# Charging_Controller_STM32_Base.net
KiCad netlist of a schematic drawn in EAGLE
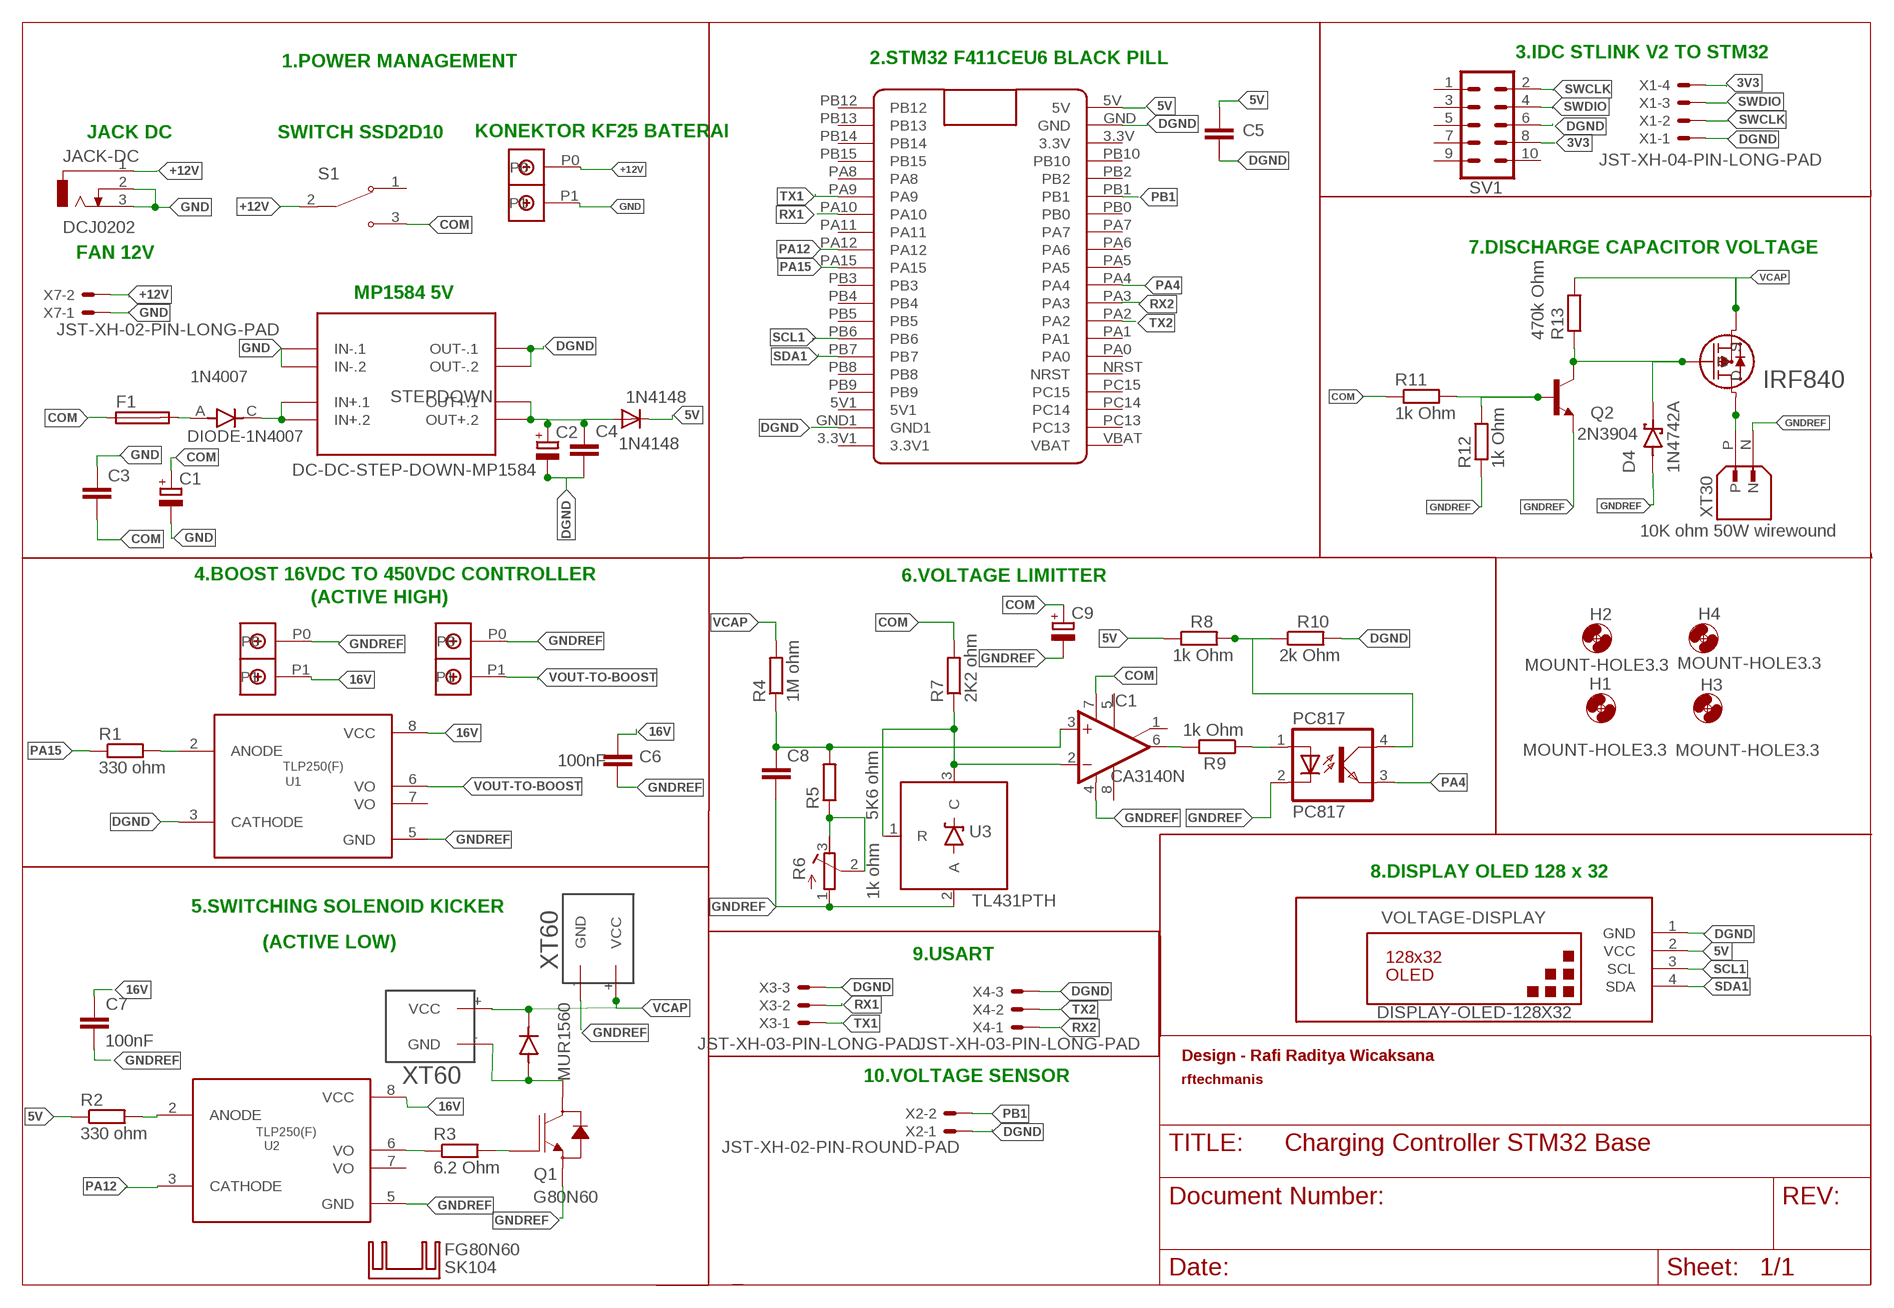
[diagram p0: schematic, sheet 1, part 1 of 2]
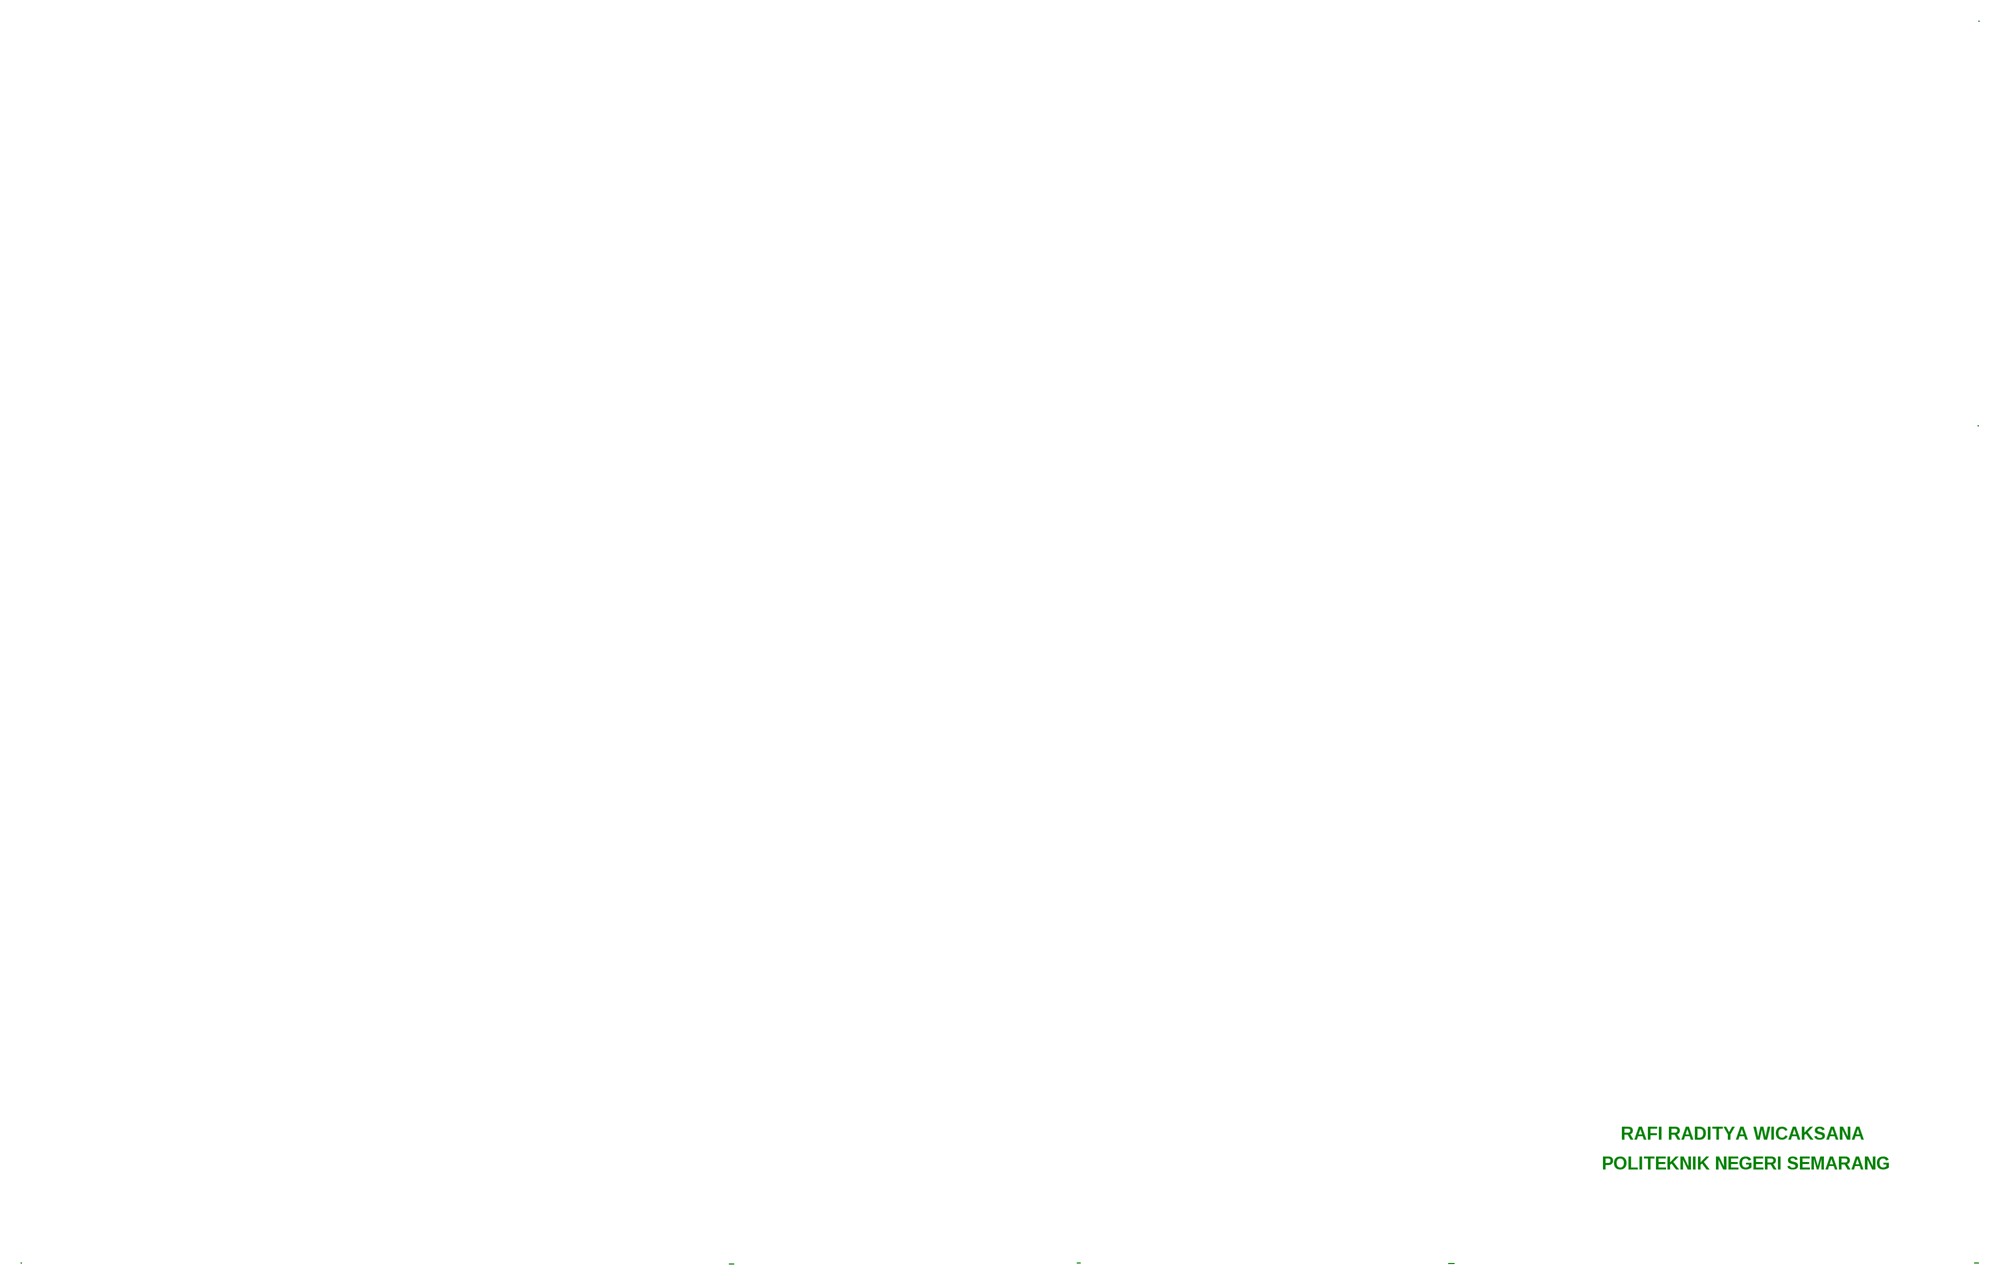
[diagram p1: schematic, sheet 1, part 2 of 2]

(export (version "E")
  (design (tool "Eeschema 10.0.6"))
  (components
    (comp (ref "1N4007")
      (value "DIODE-1N4007")
      (footprint "eagle-import:DIOAD1060W80L520D270")
      (fields (field (name "MF") "Diotec Semiconductor") (field (name "MP") "1N4007"))
      (libsource (lib "eagle-import") (part "DIODE-1N4007"))
    )
    (comp (ref "1N4148")
      (value "1N4148")
      (footprint "eagle-import:DO35-10")
      (libsource (lib "eagle-import") (part "1N4148"))
    )
    (comp (ref "C1")
      (value "CPOL-EUE3.5-8")
      (footprint "eagle-import:E3,5-8")
      (libsource (lib "eagle-import") (part "CPOL-EUE3.5-8"))
    )
    (comp (ref "C2")
      (value "CPOL-EUE3.5-8")
      (footprint "eagle-import:E3,5-8")
      (libsource (lib "eagle-import") (part "CPOL-EUE3.5-8"))
    )
    (comp (ref "C3")
      (value "C-EU050-030X075")
      (footprint "eagle-import:C050-030X075")
      (libsource (lib "eagle-import") (part "C-EU050-030X075"))
    )
    (comp (ref "C4")
      (value "C-EU050-030X075")
      (footprint "eagle-import:C050-030X075")
      (libsource (lib "eagle-import") (part "C-EU050-030X075"))
    )
    (comp (ref "C5")
      (value "C-EU050-030X075")
      (footprint "eagle-import:C050-030X075")
      (libsource (lib "eagle-import") (part "C-EU050-030X075"))
    )
    (comp (ref "C6")
      (value "100nF")
      (footprint "eagle-import:C050-030X075")
      (libsource (lib "eagle-import") (part "C-EU050-030X075"))
    )
    (comp (ref "C7")
      (value "100nF")
      (footprint "eagle-import:C050-030X075")
      (libsource (lib "eagle-import") (part "C-EU050-030X075"))
    )
    (comp (ref "C8")
      (value "C-EU050-035X075")
      (footprint "eagle-import:C050-035X075")
      (libsource (lib "eagle-import") (part "C-EU050-035X075"))
    )
    (comp (ref "C9")
      (value "CPOL-EUE2-5")
      (footprint "eagle-import:E2-5")
      (libsource (lib "eagle-import") (part "CPOL-EUE2-5"))
    )
    (comp (ref "D4")
      (value "1N4742A")
      (footprint "eagle-import:DIOAD1036W78L463D237")
      (fields (field (name "MF") "ON"))
      (libsource (lib "eagle-import") (part "1N4742A"))
    )
    (comp (ref "F1")
      (value "SH25")
      (footprint "eagle-import:SH25")
      (fields (field (name "MF") "SCHURTER") (field (name "MPN") "0031.8211"))
      (libsource (lib "eagle-import") (part "SH25"))
    )
    (comp (ref "FG80N60")
      (value "SK104")
      (footprint "eagle-import:SK104")
      (libsource (lib "eagle-import") (part "SK104"))
    )
    (comp (ref "H1")
      (value "MOUNT-HOLE3.3")
      (footprint "eagle-import:3,3")
      (libsource (lib "eagle-import") (part "MOUNT-HOLE3.3"))
    )
    (comp (ref "H2")
      (value "MOUNT-HOLE3.3")
      (footprint "eagle-import:3,3")
      (libsource (lib "eagle-import") (part "MOUNT-HOLE3.3"))
    )
    (comp (ref "H3")
      (value "MOUNT-HOLE3.3")
      (footprint "eagle-import:3,3")
      (libsource (lib "eagle-import") (part "MOUNT-HOLE3.3"))
    )
    (comp (ref "H4")
      (value "MOUNT-HOLE3.3")
      (footprint "eagle-import:3,3")
      (libsource (lib "eagle-import") (part "MOUNT-HOLE3.3"))
    )
    (comp (ref "IC1")
      (value "CA3140N")
      (footprint "eagle-import:DIL08")
      (libsource (lib "eagle-import") (part "CA3140N"))
    )
    (comp (ref "JACK-DC")
      (value "DCJ0202")
      (footprint "eagle-import:DCJ0202")
      (libsource (lib "eagle-import") (part "DCJ0202"))
    )
    (comp (ref "KF25_2PIN3")
      (value "KF25_2PIN")
      (footprint "eagle-import:KF25_2PIN")
      (libsource (lib "eagle-import") (part "KF25_2PIN"))
    )
    (comp (ref "KF25_2PIN4")
      (value "KF25_2PIN")
      (footprint "eagle-import:KF25_2PIN")
      (libsource (lib "eagle-import") (part "KF25_2PIN"))
    )
    (comp (ref "MUR1560")
      (value "MUR1560")
      (footprint "eagle-import:TO508P997X444X1905-2")
      (fields (field (name "MF") "Diotec Semiconductor"))
      (libsource (lib "eagle-import") (part "MUR1560"))
    )
    (comp (ref "PC817")
      (value "PC817")
      (footprint "eagle-import:DIL04")
      (libsource (lib "eagle-import") (part "PC817"))
    )
    (comp (ref "Q1")
      (value "G80N60")
      (footprint "eagle-import:TO544P1613X521X2557-3")
      (fields (field (name "MF") "Infineon Technologies"))
      (libsource (lib "eagle-import") (part "G80N60"))
    )
    (comp (ref "Q2")
      (value "2N3904")
      (footprint "eagle-import:TO92")
      (libsource (lib "eagle-import") (part "2N3904"))
    )
    (comp (ref "R1")
      (value "330 ohm")
      (footprint "eagle-import:0204_7")
      (libsource (lib "eagle-import") (part "R-EU_0204/7"))
    )
    (comp (ref "R2")
      (value "330 ohm")
      (footprint "eagle-import:0204_7")
      (libsource (lib "eagle-import") (part "R-EU_0204/7"))
    )
    (comp (ref "R3")
      (value "6.2 Ohm")
      (footprint "eagle-import:0411_12")
      (libsource (lib "eagle-import") (part "R-EU_0411/12"))
    )
    (comp (ref "R4")
      (value "1M ohm")
      (footprint "eagle-import:0411_12")
      (libsource (lib "eagle-import") (part "R-EU_0411/12"))
    )
    (comp (ref "R5")
      (value "5K6 ohm")
      (footprint "eagle-import:0411_12")
      (libsource (lib "eagle-import") (part "R-EU_0411/12"))
    )
    (comp (ref "R6")
      (value "1k ohm")
      (footprint "eagle-import:RTRIM64X")
      (libsource (lib "eagle-import") (part "R-TRIMM64X"))
    )
    (comp (ref "R7")
      (value "2K2 ohm")
      (footprint "eagle-import:0207_10")
      (libsource (lib "eagle-import") (part "R-EU_0207/10"))
    )
    (comp (ref "R8")
      (value "1k Ohm")
      (footprint "eagle-import:0207_10")
      (libsource (lib "eagle-import") (part "R-EU_0207/10"))
    )
    (comp (ref "R9")
      (value "1k Ohm")
      (footprint "eagle-import:0207_10")
      (libsource (lib "eagle-import") (part "R-EU_0207/10"))
    )
    (comp (ref "R10")
      (value "2k Ohm")
      (footprint "eagle-import:0207_10")
      (libsource (lib "eagle-import") (part "R-EU_0207/10"))
    )
    (comp (ref "R11")
      (value "1k Ohm")
      (footprint "eagle-import:0204_7")
      (libsource (lib "eagle-import") (part "R-EU_0204/7"))
    )
    (comp (ref "R12")
      (value "1k Ohm")
      (footprint "eagle-import:0204_7")
      (libsource (lib "eagle-import") (part "R-EU_0204/7"))
    )
    (comp (ref "R13")
      (value "470k Ohm")
      (footprint "eagle-import:0204_7")
      (libsource (lib "eagle-import") (part "R-EU_0204/7"))
    )
    (comp (ref "S1")
      (value "1103M2S3CQE2")
      (footprint "eagle-import:SW_1103M2S3CQE2")
      (fields (field (name "MF") "C&K"))
      (libsource (lib "eagle-import") (part "1103M2S3CQE2"))
    )
    (comp (ref "STEPDOWN")
      (value "DC-DC-STEP-DOWN-MP1584")
      (footprint "eagle-import:DC-DC-STEP-DOWN-MP1584")
      (libsource (lib "eagle-import") (part "DC-DC-STEP-DOWN-MP1584"))
    )
    (comp (ref "SV1")
      (value "ML10")
      (footprint "eagle-import:ML10")
      (libsource (lib "eagle-import") (part "ML10"))
    )
    (comp (ref "U$2")
      (value "KF25_2PIN")
      (footprint "eagle-import:KF25_2PIN")
      (libsource (lib "eagle-import") (part "KF25_2PIN"))
    )
    (comp (ref "U$3")
      (value "BLACK_PILL")
      (footprint "eagle-import:BLACK_PILL")
      (libsource (lib "eagle-import") (part "BLACK_PILL"))
    )
    (comp (ref "U$4")
      (value "XT60")
      (footprint "eagle-import:XT60")
      (libsource (lib "eagle-import") (part "XT60"))
    )
    (comp (ref "U$5")
      (value "XT60")
      (footprint "eagle-import:XT60")
      (libsource (lib "eagle-import") (part "XT60"))
    )
    (comp (ref "U1")
      (value "TLP250(F)")
      (footprint "eagle-import:DIP1016W50P254L966H380Q8P")
      (fields (field (name "MF") "Toshiba"))
      (libsource (lib "eagle-import") (part "TLP250(F)"))
    )
    (comp (ref "U2")
      (value "TLP250(F)")
      (footprint "eagle-import:DIP1016W50P254L966H380Q8P")
      (fields (field (name "MF") "Toshiba"))
      (libsource (lib "eagle-import") (part "TLP250(F)"))
    )
    (comp (ref "U3")
      (value "TL431PTH")
      (footprint "eagle-import:TO-92")
      (fields (field (name "MF") "onsemi") (field (name "MP") "TL431"))
      (libsource (lib "eagle-import") (part "TL431PTH"))
    )
    (comp (ref "U4")
      (value "IRF840")
      (footprint "eagle-import:TO220AB_VIS")
      (fields (field (name "COPYRIGHT") "Copyright (C) 2026 Ultra Librarian. All rights reserved."))
      (libsource (lib "eagle-import") (part "IRF840"))
    )
    (comp (ref "VOLTAGE-DISPLAY")
      (value "DISPLAY-OLED-128X32")
      (footprint "eagle-import:DISPLAY-OLED-128X32")
      (libsource (lib "eagle-import") (part "DISPLAY-OLED-128X32"))
    )
    (comp (ref "X1")
      (value "JST-XH-04-PIN-LONG-PAD")
      (footprint "eagle-import:JST-XH-04-PACKAGE-LONG-PAD")
      (libsource (lib "eagle-import") (part "JST-XH-04-PIN-LONG-PAD"))
    )
    (comp (ref "X2")
      (value "JST-XH-02-PIN-ROUND-PAD")
      (footprint "eagle-import:JST-XH-02-PACKAGE-ROUND-PAD")
      (libsource (lib "eagle-import") (part "JST-XH-02-PIN-ROUND-PAD"))
    )
    (comp (ref "X3")
      (value "JST-XH-03-PIN-LONG-PAD")
      (footprint "eagle-import:JST-XH-03-PACKAGE-LONG-PAD")
      (libsource (lib "eagle-import") (part "JST-XH-03-PIN-LONG-PAD"))
    )
    (comp (ref "X4")
      (value "JST-XH-03-PIN-LONG-PAD")
      (footprint "eagle-import:JST-XH-03-PACKAGE-LONG-PAD")
      (libsource (lib "eagle-import") (part "JST-XH-03-PIN-LONG-PAD"))
    )
    (comp (ref "X7")
      (value "JST-XH-02-PIN-LONG-PAD")
      (footprint "eagle-import:JST-XH-02-PACKAGE-LONG-PAD")
      (libsource (lib "eagle-import") (part "JST-XH-02-PIN-LONG-PAD"))
    )
    (comp (ref "XT30")
      (value "10K ohm 50W wirewound")
      (footprint "eagle-import:AMASS_XT30PW-M")
      (fields (field (name "MF") "AMASS") (field (name "MP") "XT30PW-M"))
      (libsource (lib "eagle-import") (part "XT30PW-M"))
    )
  )
  (nets
    (net (code "1") (name "+12V") (class "Default")
      (node (ref "JACK-DC") (pin "1") (pinfunction "1_1") (pintype "passive"))
      (node (ref "S1") (pin "2") (pinfunction "2_2") (pintype "passive"))
      (node (ref "U$2") (pin "P0") (pinfunction "P0_P0") (pintype "bidirectional"))
      (node (ref "X7") (pin "2") (pinfunction "S_2") (pintype "passive"))
    )
    (net (code "2") (name "3V3") (class "Default")
      (node (ref "SV1") (pin "8") (pinfunction "8_8") (pintype "passive"))
      (node (ref "X1") (pin "4") (pinfunction "S_4") (pintype "passive"))
    )
    (net (code "3") (name "5V") (class "Default")
      (node (ref "1N4148") (pin "C") (pinfunction "C_C") (pintype "passive"))
      (node (ref "C5") (pin "1") (pinfunction "1_1") (pintype "passive"))
      (node (ref "R2") (pin "1") (pinfunction "1_1") (pintype "passive"))
      (node (ref "R8") (pin "1") (pinfunction "1_1") (pintype "passive"))
      (node (ref "U$3") (pin "5V") (pinfunction "5V_5V") (pintype "power_in"))
      (node (ref "VOLTAGE-DISPLAY") (pin "2") (pinfunction "VCC_2") (pintype "power_in"))
    )
    (net (code "4") (name "16V") (class "Default")
      (node (ref "C6") (pin "1") (pinfunction "1_1") (pintype "passive"))
      (node (ref "C7") (pin "1") (pinfunction "1_1") (pintype "passive"))
      (node (ref "KF25_2PIN3") (pin "P1") (pinfunction "P1_P1") (pintype "bidirectional"))
      (node (ref "U1") (pin "8") (pinfunction "VCC_8") (pintype "power_in"))
      (node (ref "U2") (pin "8") (pinfunction "VCC_8") (pintype "power_in"))
    )
    (net (code "5") (name "COM") (class "Default")
      (node (ref "C1") (pin "+") (pinfunction "+_+") (pintype "passive"))
      (node (ref "C3") (pin "2") (pinfunction "2_2") (pintype "passive"))
      (node (ref "C9") (pin "+") (pinfunction "+_+") (pintype "passive"))
      (node (ref "F1") (pin "1") (pinfunction "1_1") (pintype "passive"))
      (node (ref "IC1") (pin "7") (pinfunction "V+_7") (pintype "power_in"))
      (node (ref "R11") (pin "1") (pinfunction "1_1") (pintype "passive"))
      (node (ref "R7") (pin "2") (pinfunction "2_2") (pintype "passive"))
      (node (ref "S1") (pin "3") (pinfunction "3_3") (pintype "passive"))
    )
    (net (code "6") (name "DGND") (class "Default")
      (node (ref "C2") (pin "-") (pinfunction "-_-") (pintype "passive"))
      (node (ref "C4") (pin "2") (pinfunction "2_2") (pintype "passive"))
      (node (ref "C5") (pin "2") (pinfunction "2_2") (pintype "passive"))
      (node (ref "R10") (pin "2") (pinfunction "2_2") (pintype "passive"))
      (node (ref "STEPDOWN") (pin "OUT-.1") (pinfunction "OUT-.1_OUT-.1") (pintype "bidirectional"))
      (node (ref "STEPDOWN") (pin "OUT-.2") (pinfunction "OUT-.2_OUT-.2") (pintype "bidirectional"))
      (node (ref "SV1") (pin "6") (pinfunction "6_6") (pintype "passive"))
      (node (ref "U$3") (pin "GND") (pinfunction "GND_GND") (pintype "bidirectional"))
      (node (ref "U$3") (pin "GND1") (pinfunction "GND1_GND1") (pintype "bidirectional"))
      (node (ref "U1") (pin "3") (pinfunction "CATHODE_3") (pintype "passive"))
      (node (ref "VOLTAGE-DISPLAY") (pin "1") (pinfunction "GND_1") (pintype "power_in"))
      (node (ref "X1") (pin "1") (pinfunction "S_1") (pintype "passive"))
      (node (ref "X2") (pin "1") (pinfunction "S_1") (pintype "passive"))
      (node (ref "X3") (pin "3") (pinfunction "S_3") (pintype "passive"))
      (node (ref "X4") (pin "3") (pinfunction "S_3") (pintype "passive"))
    )
    (net (code "7") (name "GND") (class "Default")
      (node (ref "C1") (pin "-") (pinfunction "-_-") (pintype "passive"))
      (node (ref "C3") (pin "1") (pinfunction "1_1") (pintype "passive"))
      (node (ref "JACK-DC") (pin "2") (pinfunction "2_2") (pintype "passive"))
      (node (ref "JACK-DC") (pin "3") (pinfunction "3_3") (pintype "passive"))
      (node (ref "STEPDOWN") (pin "IN-.1") (pinfunction "IN-.1_IN-.1") (pintype "bidirectional"))
      (node (ref "STEPDOWN") (pin "IN-.2") (pinfunction "IN-.2_IN-.2") (pintype "bidirectional"))
      (node (ref "U$2") (pin "P1") (pinfunction "P1_P1") (pintype "bidirectional"))
      (node (ref "X7") (pin "1") (pinfunction "S_1") (pintype "passive"))
    )
    (net (code "8") (name "GNDREF") (class "Default")
      (node (ref "C6") (pin "2") (pinfunction "2_2") (pintype "passive"))
      (node (ref "C7") (pin "2") (pinfunction "2_2") (pintype "passive"))
      (node (ref "C8") (pin "2") (pinfunction "2_2") (pintype "passive"))
      (node (ref "C9") (pin "-") (pinfunction "-_-") (pintype "passive"))
      (node (ref "D4") (pin "2") (pinfunction "A_2") (pintype "passive"))
      (node (ref "IC1") (pin "4") (pinfunction "V-_4") (pintype "power_in"))
      (node (ref "KF25_2PIN3") (pin "P0") (pinfunction "P0_P0") (pintype "bidirectional"))
      (node (ref "KF25_2PIN4") (pin "P0") (pinfunction "P0_P0") (pintype "bidirectional"))
      (node (ref "PC817") (pin "2") (pinfunction "C_2") (pintype "passive"))
      (node (ref "Q1") (pin "3") (pinfunction "E_3") (pintype "passive"))
      (node (ref "Q2") (pin "3") (pinfunction "E_3") (pintype "passive"))
      (node (ref "R12") (pin "1") (pinfunction "1_1") (pintype "passive"))
      (node (ref "R6") (pin "1") (pinfunction "A_1") (pintype "passive"))
      (node (ref "U$4") (pin "-") (pinfunction "GND_-") (pintype "bidirectional"))
      (node (ref "U1") (pin "5") (pinfunction "GND_5") (pintype "power_in"))
      (node (ref "U2") (pin "5") (pinfunction "GND_5") (pintype "power_in"))
      (node (ref "U3") (pin "2") (pinfunction "A_2") (pintype "bidirectional"))
      (node (ref "XT30") (pin "N") (pinfunction "N_N") (pintype "power_in"))
    )
    (net (code "9") (name "Net-(1N4007-PadA)") (class "Default")
      (node (ref "1N4007") (pin "A") (pinfunction "A_A") (pintype "passive"))
      (node (ref "F1") (pin "2") (pinfunction "2_2") (pintype "passive"))
    )
    (net (code "10") (name "Net-(1N4007-PadC)") (class "Default")
      (node (ref "1N4007") (pin "C") (pinfunction "C_C") (pintype "passive"))
      (node (ref "STEPDOWN") (pin "IN+.1") (pinfunction "IN+.1_IN+.1") (pintype "bidirectional"))
      (node (ref "STEPDOWN") (pin "IN+.2") (pinfunction "IN+.2_IN+.2") (pintype "bidirectional"))
    )
    (net (code "11") (name "Net-(1N4148-PadA)") (class "Default")
      (node (ref "1N4148") (pin "A") (pinfunction "A_A") (pintype "passive"))
      (node (ref "C2") (pin "+") (pinfunction "+_+") (pintype "passive"))
      (node (ref "C4") (pin "1") (pinfunction "1_1") (pintype "passive"))
      (node (ref "STEPDOWN") (pin "OUT+.1") (pinfunction "OUT+.1_OUT+.1") (pintype "bidirectional"))
      (node (ref "STEPDOWN") (pin "OUT+.2") (pinfunction "OUT+.2_OUT+.2") (pintype "bidirectional"))
    )
    (net (code "12") (name "Net-(D4-K)") (class "Default")
      (node (ref "D4") (pin "1") (pinfunction "K_1") (pintype "passive"))
      (node (ref "Q2") (pin "1") (pinfunction "C_1") (pintype "passive"))
      (node (ref "R13") (pin "1") (pinfunction "1_1") (pintype "passive"))
      (node (ref "U4") (pin "1") (pinfunction "G_1") (pintype "passive"))
    )
    (net (code "13") (name "Net-(IC1-+IN)") (class "Default")
      (node (ref "C8") (pin "1") (pinfunction "1_1") (pintype "passive"))
      (node (ref "IC1") (pin "3") (pinfunction "+IN_3") (pintype "input"))
      (node (ref "R4") (pin "1") (pinfunction "1_1") (pintype "passive"))
      (node (ref "R5") (pin "2") (pinfunction "2_2") (pintype "passive"))
    )
    (net (code "14") (name "Net-(IC1--IN)") (class "Default")
      (node (ref "IC1") (pin "2") (pinfunction "-IN_2") (pintype "input"))
      (node (ref "R7") (pin "1") (pinfunction "1_1") (pintype "passive"))
      (node (ref "U3") (pin "1") (pinfunction "R_1") (pintype "bidirectional"))
      (node (ref "U3") (pin "3") (pinfunction "C_3") (pintype "bidirectional"))
    )
    (net (code "15") (name "Net-(IC1-OUT)") (class "Default")
      (node (ref "IC1") (pin "6") (pinfunction "OUT_6") (pintype "output"))
      (node (ref "R9") (pin "2") (pinfunction "2_2") (pintype "passive"))
    )
    (net (code "16") (name "Net-(MUR1560-A)") (class "Default")
      (node (ref "MUR1560") (pin "3") (pinfunction "A_3") (pintype "passive"))
      (node (ref "Q1") (pin "2") (pinfunction "C_2") (pintype "passive"))
      (node (ref "U$5") (pin "-") (pinfunction "GND_-") (pintype "bidirectional"))
    )
    (net (code "17") (name "Net-(PC817-A)") (class "Default")
      (node (ref "PC817") (pin "1") (pinfunction "A_1") (pintype "passive"))
      (node (ref "R9") (pin "1") (pinfunction "1_1") (pintype "passive"))
    )
    (net (code "18") (name "Net-(PC817-COL)") (class "Default")
      (node (ref "PC817") (pin "4") (pinfunction "COL_4") (pintype "passive"))
      (node (ref "R10") (pin "1") (pinfunction "1_1") (pintype "passive"))
      (node (ref "R8") (pin "2") (pinfunction "2_2") (pintype "passive"))
    )
    (net (code "19") (name "Net-(Q1-G)") (class "Default")
      (node (ref "Q1") (pin "1") (pinfunction "G_1") (pintype "passive"))
      (node (ref "R3") (pin "2") (pinfunction "2_2") (pintype "passive"))
    )
    (net (code "20") (name "Net-(Q2-B)") (class "Default")
      (node (ref "Q2") (pin "2") (pinfunction "B_2") (pintype "passive"))
      (node (ref "R11") (pin "2") (pinfunction "2_2") (pintype "passive"))
      (node (ref "R12") (pin "2") (pinfunction "2_2") (pintype "passive"))
    )
    (net (code "21") (name "Net-(R3-Pad1)") (class "Default")
      (node (ref "R3") (pin "1") (pinfunction "1_1") (pintype "passive"))
      (node (ref "U2") (pin "6") (pinfunction "VO_6") (pintype "output"))
    )
    (net (code "22") (name "Net-(R6-E)") (class "Default")
      (node (ref "R5") (pin "1") (pinfunction "1_1") (pintype "passive"))
      (node (ref "R6") (pin "2") (pinfunction "S_2") (pintype "passive"))
      (node (ref "R6") (pin "3") (pinfunction "E_3") (pintype "passive"))
    )
    (net (code "23") (name "Net-(U1-ANODE)") (class "Default")
      (node (ref "R1") (pin "2") (pinfunction "2_2") (pintype "passive"))
      (node (ref "U1") (pin "2") (pinfunction "ANODE_2") (pintype "passive"))
    )
    (net (code "24") (name "Net-(U2-ANODE)") (class "Default")
      (node (ref "R2") (pin "2") (pinfunction "2_2") (pintype "passive"))
      (node (ref "U2") (pin "2") (pinfunction "ANODE_2") (pintype "passive"))
    )
    (net (code "25") (name "Net-(U4-D)") (class "Default")
      (node (ref "U4") (pin "2") (pinfunction "D_2") (pintype "passive"))
      (node (ref "XT30") (pin "P") (pinfunction "P_P") (pintype "power_in"))
    )
    (net (code "26") (name "PA4") (class "Default")
      (node (ref "PC817") (pin "3") (pinfunction "EMIT_3") (pintype "passive"))
      (node (ref "U$3") (pin "PA4") (pinfunction "PA4_PA4") (pintype "bidirectional"))
    )
    (net (code "27") (name "PA12") (class "Default")
      (node (ref "U$3") (pin "PA12") (pinfunction "PA12_PA12") (pintype "bidirectional"))
      (node (ref "U2") (pin "3") (pinfunction "CATHODE_3") (pintype "passive"))
    )
    (net (code "28") (name "PA15") (class "Default")
      (node (ref "R1") (pin "1") (pinfunction "1_1") (pintype "passive"))
      (node (ref "U$3") (pin "PA15") (pinfunction "PA15_PA15") (pintype "bidirectional"))
    )
    (net (code "29") (name "PB1") (class "Default")
      (node (ref "U$3") (pin "PB1") (pinfunction "PB1_PB1") (pintype "bidirectional"))
      (node (ref "X2") (pin "2") (pinfunction "S_2") (pintype "passive"))
    )
    (net (code "30") (name "RX1") (class "Default")
      (node (ref "U$3") (pin "PA10") (pinfunction "PA10_PA10") (pintype "bidirectional"))
      (node (ref "X3") (pin "2") (pinfunction "S_2") (pintype "passive"))
    )
    (net (code "31") (name "RX2") (class "Default")
      (node (ref "U$3") (pin "PA3") (pinfunction "PA3_PA3") (pintype "bidirectional"))
      (node (ref "X4") (pin "1") (pinfunction "S_1") (pintype "passive"))
    )
    (net (code "32") (name "SCL1") (class "Default")
      (node (ref "U$3") (pin "PB6") (pinfunction "PB6_PB6") (pintype "bidirectional"))
      (node (ref "VOLTAGE-DISPLAY") (pin "3") (pinfunction "SCL_3") (pintype "bidirectional"))
    )
    (net (code "33") (name "SDA1") (class "Default")
      (node (ref "U$3") (pin "PB7") (pinfunction "PB7_PB7") (pintype "bidirectional"))
      (node (ref "VOLTAGE-DISPLAY") (pin "4") (pinfunction "SDA_4") (pintype "bidirectional"))
    )
    (net (code "34") (name "SWCLK") (class "Default")
      (node (ref "SV1") (pin "2") (pinfunction "2_2") (pintype "passive"))
      (node (ref "X1") (pin "2") (pinfunction "S_2") (pintype "passive"))
    )
    (net (code "35") (name "SWDIO") (class "Default")
      (node (ref "SV1") (pin "4") (pinfunction "4_4") (pintype "passive"))
      (node (ref "X1") (pin "3") (pinfunction "S_3") (pintype "passive"))
    )
    (net (code "36") (name "TX1") (class "Default")
      (node (ref "U$3") (pin "PA9") (pinfunction "PA9_PA9") (pintype "bidirectional"))
      (node (ref "X3") (pin "1") (pinfunction "S_1") (pintype "passive"))
    )
    (net (code "37") (name "TX2") (class "Default")
      (node (ref "U$3") (pin "PA2") (pinfunction "PA2_PA2") (pintype "bidirectional"))
      (node (ref "X4") (pin "2") (pinfunction "S_2") (pintype "passive"))
    )
    (net (code "38") (name "VCAP") (class "Default")
      (node (ref "MUR1560") (pin "1") (pinfunction "K_1") (pintype "passive"))
      (node (ref "R13") (pin "2") (pinfunction "2_2") (pintype "passive"))
      (node (ref "R4") (pin "2") (pinfunction "2_2") (pintype "passive"))
      (node (ref "U$4") (pin "+") (pinfunction "VCC_+") (pintype "bidirectional"))
      (node (ref "U$5") (pin "+") (pinfunction "VCC_+") (pintype "bidirectional"))
      (node (ref "U4") (pin "3") (pinfunction "S_3") (pintype "passive"))
    )
    (net (code "39") (name "VOUT-TO-BOOST") (class "Default")
      (node (ref "KF25_2PIN4") (pin "P1") (pinfunction "P1_P1") (pintype "bidirectional"))
      (node (ref "U1") (pin "6") (pinfunction "VO_6") (pintype "output"))
    )
    (net (code "40") (name "unconnected-(IC1-CMP-Pad8)") (class "Default")
      (node (ref "IC1") (pin "8") (pinfunction "CMP_8") (pintype "passive"))
    )
    (net (code "41") (name "unconnected-(IC1-ON-Pad5)") (class "Default")
      (node (ref "IC1") (pin "5") (pinfunction "ON_5") (pintype "passive"))
    )
    (net (code "42") (name "unconnected-(IC1-ON{slash}CMP-Pad1)") (class "Default")
      (node (ref "IC1") (pin "1") (pinfunction "ON/CMP_1") (pintype "passive"))
    )
    (net (code "43") (name "unconnected-(S1-Pad1)") (class "Default")
      (node (ref "S1") (pin "1") (pinfunction "1_1") (pintype "passive"))
    )
    (net (code "44") (name "unconnected-(SV1-Pad1)") (class "Default")
      (node (ref "SV1") (pin "1") (pinfunction "1_1") (pintype "passive"))
    )
    (net (code "45") (name "unconnected-(SV1-Pad3)") (class "Default")
      (node (ref "SV1") (pin "3") (pinfunction "3_3") (pintype "passive"))
    )
    (net (code "46") (name "unconnected-(SV1-Pad5)") (class "Default")
      (node (ref "SV1") (pin "5") (pinfunction "5_5") (pintype "passive"))
    )
    (net (code "47") (name "unconnected-(SV1-Pad7)") (class "Default")
      (node (ref "SV1") (pin "7") (pinfunction "7_7") (pintype "passive"))
    )
    (net (code "48") (name "unconnected-(SV1-Pad9)") (class "Default")
      (node (ref "SV1") (pin "9") (pinfunction "9_9") (pintype "passive"))
    )
    (net (code "49") (name "unconnected-(SV1-Pad10)") (class "Default")
      (node (ref "SV1") (pin "10") (pinfunction "10_10") (pintype "passive"))
    )
    (net (code "50") (name "unconnected-(U$3-Pad3.3V)") (class "Default")
      (node (ref "U$3") (pin "3.3V") (pinfunction "3.3V_3.3V") (pintype "bidirectional"))
    )
    (net (code "51") (name "unconnected-(U$3-Pad3.3V1)") (class "Default")
      (node (ref "U$3") (pin "3.3V1") (pinfunction "3.3V1_3.3V1") (pintype "bidirectional"))
    )
    (net (code "52") (name "unconnected-(U$3-Pad5V1)") (class "Default")
      (node (ref "U$3") (pin "5V1") (pinfunction "5V1_5V1") (pintype "bidirectional"))
    )
    (net (code "53") (name "unconnected-(U$3-PadNRST)") (class "Default")
      (node (ref "U$3") (pin "NRST") (pinfunction "NRST_NRST") (pintype "bidirectional"))
    )
    (net (code "54") (name "unconnected-(U$3-PadPA0)") (class "Default")
      (node (ref "U$3") (pin "PA0") (pinfunction "PA0_PA0") (pintype "bidirectional"))
    )
    (net (code "55") (name "unconnected-(U$3-PadPA1)") (class "Default")
      (node (ref "U$3") (pin "PA1") (pinfunction "PA1_PA1") (pintype "bidirectional"))
    )
    (net (code "56") (name "unconnected-(U$3-PadPA5)") (class "Default")
      (node (ref "U$3") (pin "PA5") (pinfunction "PA5_PA5") (pintype "bidirectional"))
    )
    (net (code "57") (name "unconnected-(U$3-PadPA6)") (class "Default")
      (node (ref "U$3") (pin "PA6") (pinfunction "PA6_PA6") (pintype "bidirectional"))
    )
    (net (code "58") (name "unconnected-(U$3-PadPA7)") (class "Default")
      (node (ref "U$3") (pin "PA7") (pinfunction "PA7_PA7") (pintype "bidirectional"))
    )
    (net (code "59") (name "unconnected-(U$3-PadPA8)") (class "Default")
      (node (ref "U$3") (pin "PA8") (pinfunction "PA8_PA8") (pintype "bidirectional"))
    )
    (net (code "60") (name "unconnected-(U$3-PadPA11)") (class "Default")
      (node (ref "U$3") (pin "PA11") (pinfunction "PA11_PA11") (pintype "bidirectional"))
    )
    (net (code "61") (name "unconnected-(U$3-PadPB0)") (class "Default")
      (node (ref "U$3") (pin "PB0") (pinfunction "PB0_PB0") (pintype "bidirectional"))
    )
    (net (code "62") (name "unconnected-(U$3-PadPB2)") (class "Default")
      (node (ref "U$3") (pin "PB2") (pinfunction "PB2_PB2") (pintype "bidirectional"))
    )
    (net (code "63") (name "unconnected-(U$3-PadPB3)") (class "Default")
      (node (ref "U$3") (pin "PB3") (pinfunction "PB3_PB3") (pintype "bidirectional"))
    )
    (net (code "64") (name "unconnected-(U$3-PadPB4)") (class "Default")
      (node (ref "U$3") (pin "PB4") (pinfunction "PB4_PB4") (pintype "bidirectional"))
    )
    (net (code "65") (name "unconnected-(U$3-PadPB5)") (class "Default")
      (node (ref "U$3") (pin "PB5") (pinfunction "PB5_PB5") (pintype "bidirectional"))
    )
    (net (code "66") (name "unconnected-(U$3-PadPB8)") (class "Default")
      (node (ref "U$3") (pin "PB8") (pinfunction "PB8_PB8") (pintype "bidirectional"))
    )
    (net (code "67") (name "unconnected-(U$3-PadPB9)") (class "Default")
      (node (ref "U$3") (pin "PB9") (pinfunction "PB9_PB9") (pintype "bidirectional"))
    )
    (net (code "68") (name "unconnected-(U$3-PadPB10)") (class "Default")
      (node (ref "U$3") (pin "PB10") (pinfunction "PB10_PB10") (pintype "bidirectional"))
    )
    (net (code "69") (name "unconnected-(U$3-PadPB12)") (class "Default")
      (node (ref "U$3") (pin "PB12") (pinfunction "PB12_PB12") (pintype "bidirectional"))
    )
    (net (code "70") (name "unconnected-(U$3-PadPB13)") (class "Default")
      (node (ref "U$3") (pin "PB13") (pinfunction "PB13_PB13") (pintype "bidirectional"))
    )
    (net (code "71") (name "unconnected-(U$3-PadPB14)") (class "Default")
      (node (ref "U$3") (pin "PB14") (pinfunction "PB14_PB14") (pintype "bidirectional"))
    )
    (net (code "72") (name "unconnected-(U$3-PadPB15)") (class "Default")
      (node (ref "U$3") (pin "PB15") (pinfunction "PB15_PB15") (pintype "bidirectional"))
    )
    (net (code "73") (name "unconnected-(U$3-PadPC13)") (class "Default")
      (node (ref "U$3") (pin "PC13") (pinfunction "PC13_PC13") (pintype "bidirectional"))
    )
    (net (code "74") (name "unconnected-(U$3-PadPC14)") (class "Default")
      (node (ref "U$3") (pin "PC14") (pinfunction "PC14_PC14") (pintype "bidirectional"))
    )
    (net (code "75") (name "unconnected-(U$3-PadPC15)") (class "Default")
      (node (ref "U$3") (pin "PC15") (pinfunction "PC15_PC15") (pintype "bidirectional"))
    )
    (net (code "76") (name "unconnected-(U$3-PadVBAT)") (class "Default")
      (node (ref "U$3") (pin "VBAT") (pinfunction "VBAT_VBAT") (pintype "bidirectional"))
    )
    (net (code "77") (name "unconnected-(U1-VO-Pad7)") (class "Default")
      (node (ref "U1") (pin "7") (pinfunction "VO_7") (pintype "output"))
    )
    (net (code "78") (name "unconnected-(U2-VO-Pad7)") (class "Default")
      (node (ref "U2") (pin "7") (pinfunction "VO_7") (pintype "output"))
    )
  )
)
